# I2C_Mux.net
KiCad netlist of a schematic drawn in Altium Designer
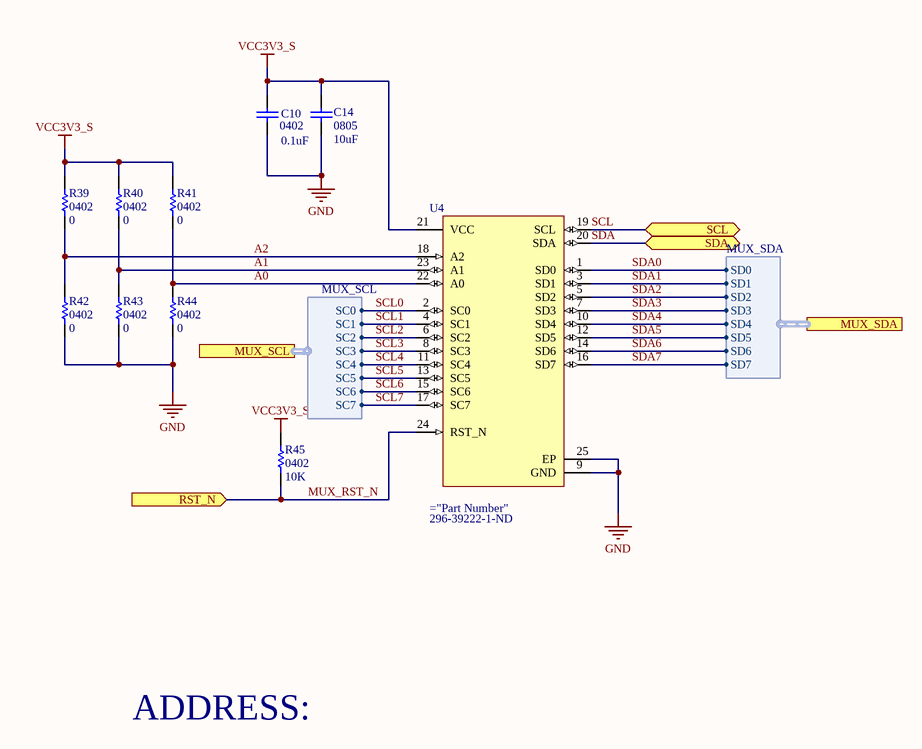
[diagram p0: I2C Mux.SchDoc]

(export (version "E")
  (design (tool "Eeschema 10.0.6"))
  (components
    (comp (ref "C10")
      (value "0402")
      (footprint "CAP0402R")
      (description "Capacitor (Semiconductor SIM Model)")
      (fields
        (field (name "ALTIUM_VALUE") "0.1uF")
        (field (name "MANUFACTURER") "Murata")
        (field (name "MANUFACTURER PART NUMBER") "GCM155R71C104KA55J")
        (field (name "PUBLISHER") "Altium Limited")
      )
      (libsource (lib "Miscellaneous Devices") (part "Cap Semi"))
    )
    (comp (ref "C14")
      (value "0805")
      (footprint "CAP0805R")
      (description "Capacitor")
      (fields
        (field (name "ALTIUM_VALUE") "10uF")
        (field (name "MANUFACTURER") "TDK")
        (field (name "MANUFACTURER PART NUMBER") "CGA4J1X7R0J106K125AC")
        (field (name "PUBLISHER") "Altium Limited")
      )
      (libsource (lib "Miscellaneous Devices") (part "Cap"))
    )
    (comp (ref "R39")
      (value "0402")
      (footprint "RES0402R")
      (description "Resistor")
      (fields
        (field (name "ALTIUM_VALUE") "0")
        (field (name "MANUFACTURER") "Panasonic")
        (field (name "MANUFACTURER PART NUMBER") "ERJ2GE0R00X")
        (field (name "PUBLISHER") "Altium Limited")
      )
      (libsource (lib "Miscellaneous Devices") (part "Res1"))
    )
    (comp (ref "R40")
      (value "0402")
      (footprint "RES0402R")
      (description "Resistor")
      (fields
        (field (name "ALTIUM_VALUE") "0")
        (field (name "MANUFACTURER") "Panasonic")
        (field (name "MANUFACTURER PART NUMBER") "ERJ2GE0R00X")
        (field (name "PUBLISHER") "Altium Limited")
      )
      (libsource (lib "Miscellaneous Devices") (part "Res1"))
    )
    (comp (ref "R41")
      (value "0402")
      (footprint "RES0402R")
      (description "Resistor")
      (fields
        (field (name "ALTIUM_VALUE") "0")
        (field (name "MANUFACTURER") "Panasonic")
        (field (name "MANUFACTURER PART NUMBER") "ERJ2GE0R00X")
        (field (name "PUBLISHER") "Altium Limited")
      )
      (libsource (lib "Miscellaneous Devices") (part "Res1"))
    )
    (comp (ref "R42")
      (value "0402")
      (footprint "RES0402R")
      (description "Resistor")
      (fields
        (field (name "ALTIUM_VALUE") "0")
        (field (name "MANUFACTURER") "Panasonic")
        (field (name "MANUFACTURER PART NUMBER") "ERJ2GE0R00X")
        (field (name "PUBLISHER") "Altium Limited")
      )
      (libsource (lib "Miscellaneous Devices") (part "Res1"))
    )
    (comp (ref "R43")
      (value "0402")
      (footprint "RES0402R")
      (description "Resistor")
      (fields
        (field (name "ALTIUM_VALUE") "0")
        (field (name "MANUFACTURER") "Panasonic")
        (field (name "MANUFACTURER PART NUMBER") "ERJ2GE0R00X")
        (field (name "PUBLISHER") "Altium Limited")
      )
      (libsource (lib "Miscellaneous Devices") (part "Res1"))
    )
    (comp (ref "R44")
      (value "0402")
      (footprint "RES0402R")
      (description "Resistor")
      (fields
        (field (name "ALTIUM_VALUE") "0")
        (field (name "MANUFACTURER") "Panasonic")
        (field (name "MANUFACTURER PART NUMBER") "ERJ2GE0R00X")
        (field (name "PUBLISHER") "Altium Limited")
      )
      (libsource (lib "Miscellaneous Devices") (part "Res1"))
    )
    (comp (ref "R45")
      (value "0402")
      (footprint "RES0402R")
      (description "Resistor")
      (fields (field (name "ALTIUM_VALUE") "10K") (field (name "PUBLISHER") "Altium Limited"))
      (libsource (lib "Miscellaneous Devices") (part "Res1"))
    )
    (comp (ref "U4")
      (value "TCA9548ARGER")
      (footprint "RGE0024C")
      (fields (field (name "SUPPLIER PART NUMBER 1") "296-39222-1-ND"))
      (libsource (lib "heron-general") (part "TCA9548ARGER"))
    )
  )
  (nets
    (net (code "3") (name "/A0") (class "Default")
      (node (ref "R41") (pin "1") (pinfunction "1_1") (pintype "passive"))
      (node (ref "R44") (pin "2") (pinfunction "2_2") (pintype "passive"))
      (node (ref "U4") (pin "22") (pinfunction "A0_22") (pintype "bidirectional"))
    )
    (net (code "4") (name "/A1") (class "Default")
      (node (ref "R40") (pin "1") (pinfunction "1_1") (pintype "passive"))
      (node (ref "R43") (pin "2") (pinfunction "2_2") (pintype "passive"))
      (node (ref "U4") (pin "23") (pinfunction "A1_23") (pintype "bidirectional"))
    )
    (net (code "5") (name "/A2") (class "Default")
      (node (ref "R39") (pin "1") (pinfunction "1_1") (pintype "passive"))
      (node (ref "R42") (pin "2") (pinfunction "2_2") (pintype "passive"))
      (node (ref "U4") (pin "18") (pinfunction "A2_18") (pintype "input"))
    )
    (net (code "6") (name "/MUX_RST_N") (class "Default")
      (node (ref "R45") (pin "1") (pinfunction "1_1") (pintype "passive"))
      (node (ref "U4") (pin "24") (pinfunction "RST_N_24") (pintype "input"))
    )
    (net (code "7") (name "/SCL") (class "Default")
      (node (ref "U4") (pin "19") (pinfunction "SCL_19") (pintype "bidirectional"))
    )
    (net (code "8") (name "/SCL0") (class "Default")
      (node (ref "U4") (pin "2") (pinfunction "SC0_2") (pintype "bidirectional"))
    )
    (net (code "9") (name "/SCL1") (class "Default")
      (node (ref "U4") (pin "4") (pinfunction "SC1_4") (pintype "bidirectional"))
    )
    (net (code "10") (name "/SCL2") (class "Default")
      (node (ref "U4") (pin "6") (pinfunction "SC2_6") (pintype "bidirectional"))
    )
    (net (code "11") (name "/SCL3") (class "Default")
      (node (ref "U4") (pin "8") (pinfunction "SC3_8") (pintype "bidirectional"))
    )
    (net (code "12") (name "/SCL4") (class "Default")
      (node (ref "U4") (pin "11") (pinfunction "SC4_11") (pintype "bidirectional"))
    )
    (net (code "13") (name "/SCL5") (class "Default")
      (node (ref "U4") (pin "13") (pinfunction "SC5_13") (pintype "bidirectional"))
    )
    (net (code "14") (name "/SCL6") (class "Default")
      (node (ref "U4") (pin "15") (pinfunction "SC6_15") (pintype "bidirectional"))
    )
    (net (code "15") (name "/SCL7") (class "Default")
      (node (ref "U4") (pin "17") (pinfunction "SC7_17") (pintype "bidirectional"))
    )
    (net (code "16") (name "/SDA") (class "Default")
      (node (ref "U4") (pin "20") (pinfunction "SDA_20") (pintype "bidirectional"))
    )
    (net (code "17") (name "/SDA0") (class "Default")
      (node (ref "U4") (pin "1") (pinfunction "SD0_1") (pintype "bidirectional"))
    )
    (net (code "18") (name "/SDA1") (class "Default")
      (node (ref "U4") (pin "3") (pinfunction "SD1_3") (pintype "bidirectional"))
    )
    (net (code "19") (name "/SDA2") (class "Default")
      (node (ref "U4") (pin "5") (pinfunction "SD2_5") (pintype "bidirectional"))
    )
    (net (code "20") (name "/SDA3") (class "Default")
      (node (ref "U4") (pin "7") (pinfunction "SD3_7") (pintype "bidirectional"))
    )
    (net (code "21") (name "/SDA4") (class "Default")
      (node (ref "U4") (pin "10") (pinfunction "SD4_10") (pintype "bidirectional"))
    )
    (net (code "22") (name "/SDA5") (class "Default")
      (node (ref "U4") (pin "12") (pinfunction "SD5_12") (pintype "bidirectional"))
    )
    (net (code "23") (name "/SDA6") (class "Default")
      (node (ref "U4") (pin "14") (pinfunction "SD6_14") (pintype "bidirectional"))
    )
    (net (code "24") (name "/SDA7") (class "Default")
      (node (ref "U4") (pin "16") (pinfunction "SD7_16") (pintype "bidirectional"))
    )
    (net (code "27") (name "GND") (class "Default")
      (node (ref "C10") (pin "1") (pinfunction "1_1") (pintype "passive"))
      (node (ref "C14") (pin "1") (pinfunction "1_1") (pintype "passive"))
      (node (ref "R42") (pin "1") (pinfunction "1_1") (pintype "passive"))
      (node (ref "R43") (pin "1") (pinfunction "1_1") (pintype "passive"))
      (node (ref "R44") (pin "1") (pinfunction "1_1") (pintype "passive"))
      (node (ref "U4") (pin "25") (pinfunction "EP_25") (pintype "power_in"))
      (node (ref "U4") (pin "9") (pinfunction "GND_9") (pintype "power_in"))
    )
    (net (code "28") (name "VCC3V3_S") (class "Default")
      (node (ref "C10") (pin "2") (pinfunction "2_2") (pintype "passive"))
      (node (ref "C14") (pin "2") (pinfunction "2_2") (pintype "passive"))
      (node (ref "R39") (pin "2") (pinfunction "2_2") (pintype "passive"))
      (node (ref "R40") (pin "2") (pinfunction "2_2") (pintype "passive"))
      (node (ref "R41") (pin "2") (pinfunction "2_2") (pintype "passive"))
      (node (ref "R45") (pin "2") (pinfunction "2_2") (pintype "passive"))
      (node (ref "U4") (pin "21") (pinfunction "VCC_21") (pintype "power_in"))
    )
  )
)
